# Lightbox_schematic_06NOV.net
KiCad netlist of a schematic drawn in EAGLE
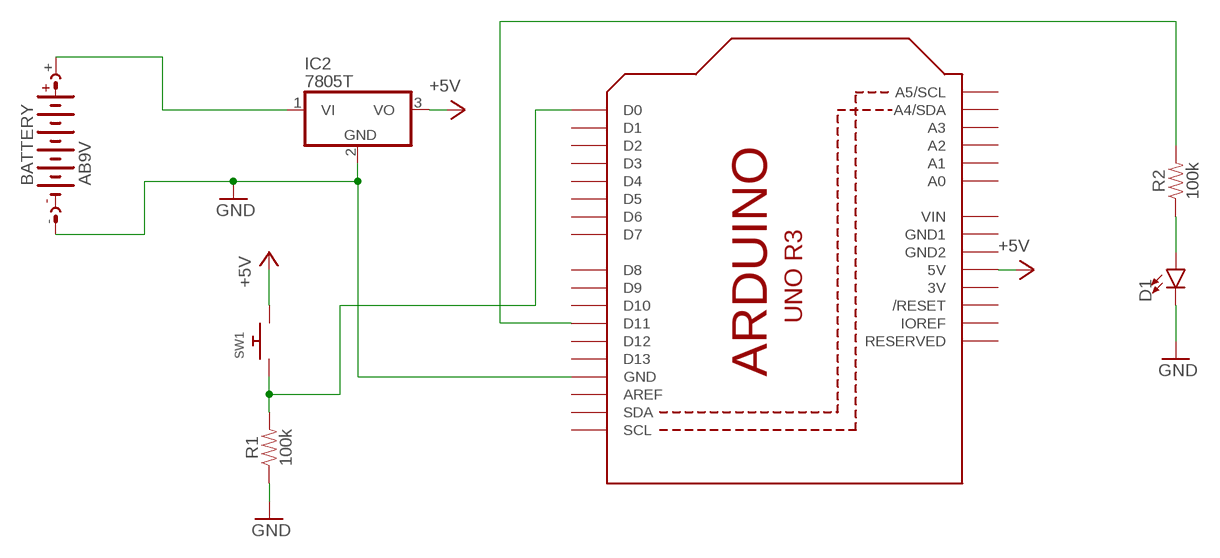
[diagram p0: schematic, sheet 1]

(export (version "E")
  (design (tool "Eeschema 10.0.6"))
  (components
    (comp (ref "BATTERY")
      (value "AB9V")
      (footprint "eagle-import:AB9V")
      (libsource (lib "eagle-import") (part "AB9V"))
    )
    (comp (ref "D1")
      (value "LED3MM")
      (footprint "eagle-import:LED_3MM")
      (libsource (lib "eagle-import") (part "LED3MM"))
    )
    (comp (ref "IC2")
      (value "7805T")
      (footprint "eagle-import:TO220H")
      (libsource (lib "eagle-import") (part "78T05"))
    )
    (comp (ref "R1")
      (value "100k")
      (footprint "eagle-import:AXIAL-0.3")
      (libsource (lib "eagle-import") (part "100KOHM-HORIZ-1/4W-1%"))
    )
    (comp (ref "R2")
      (value "100k")
      (footprint "eagle-import:AXIAL-0.3")
      (libsource (lib "eagle-import") (part "100KOHM-HORIZ-1/4W-1%"))
    )
    (comp (ref "SW1")
      (value "SWITCH_PUSHBUTTONSOFTTOUCHSMD_SJ")
      (footprint "eagle-import:PUSHBUTTON_SMD_SJ")
      (libsource (lib "eagle-import") (part "SWITCH_PUSHBUTTONSOFTTOUCHSMD_SJ"))
    )
    (comp (ref "U1")
      (value "ARDUINOR3-DIMENSION")
      (footprint "eagle-import:ARDUINOR3")
      (libsource (lib "eagle-import") (part "ARDUINOR3-DIMENSION"))
    )
  )
  (nets
    (net (code "1") (name "+5V") (class "Default")
      (node (ref "IC2") (pin "3") (pinfunction "VO_3") (pintype "passive"))
      (node (ref "SW1") (pin "P$2") (pinfunction "P$2_P$2") (pintype "passive"))
      (node (ref "U1") (pin "5V") (pinfunction "5V_5V") (pintype "power_in"))
    )
    (net (code "2") (name "/3V") (class "Default")
      (node (ref "U1") (pin "3V") (pinfunction "3V_3V") (pintype "power_in"))
    )
    (net (code "3") (name "/GND1") (class "Default")
      (node (ref "U1") (pin "GND1") (pinfunction "GND1_GND1") (pintype "power_in"))
    )
    (net (code "4") (name "/GND2") (class "Default")
      (node (ref "U1") (pin "GND2") (pinfunction "GND2_GND2") (pintype "power_in"))
    )
    (net (code "5") (name "/VIN") (class "Default")
      (node (ref "U1") (pin "VIN") (pinfunction "VIN_VIN") (pintype "power_in"))
    )
    (net (code "6") (name "GND") (class "Default")
      (node (ref "BATTERY") (pin "-") (pinfunction "-_-") (pintype "passive"))
      (node (ref "D1") (pin "K") (pinfunction "C_K") (pintype "passive"))
      (node (ref "IC2") (pin "2") (pinfunction "GND_2") (pintype "passive"))
      (node (ref "R1") (pin "P$1") (pinfunction "1_P$1") (pintype "passive"))
      (node (ref "U1") (pin "GND") (pinfunction "GND_GND") (pintype "power_in"))
    )
    (net (code "7") (name "Net-(IC2-VI)") (class "Default")
      (node (ref "BATTERY") (pin "+") (pinfunction "+_+") (pintype "passive"))
      (node (ref "IC2") (pin "1") (pinfunction "VI_1") (pintype "input"))
    )
    (net (code "8") (name "Net-(R1-2)") (class "Default")
      (node (ref "R1") (pin "P$2") (pinfunction "2_P$2") (pintype "passive"))
      (node (ref "SW1") (pin "P$1") (pinfunction "P$1_P$1") (pintype "passive"))
      (node (ref "U1") (pin "D0") (pinfunction "D0_D0") (pintype "bidirectional"))
    )
    (net (code "9") (name "Net-(R2-1)") (class "Default")
      (node (ref "D1") (pin "A") (pinfunction "A_A") (pintype "passive"))
      (node (ref "R2") (pin "P$1") (pinfunction "1_P$1") (pintype "passive"))
    )
    (net (code "10") (name "Net-(R2-2)") (class "Default")
      (node (ref "R2") (pin "P$2") (pinfunction "2_P$2") (pintype "passive"))
      (node (ref "U1") (pin "D11") (pinfunction "D11_D11") (pintype "bidirectional"))
    )
    (net (code "11") (name "unconnected-(U1-A4{slash}SDA-PadA4)") (class "Default")
      (node (ref "U1") (pin "A4") (pinfunction "A4/SDA_A4") (pintype "bidirectional"))
    )
    (net (code "12") (name "unconnected-(U1-A5{slash}SCL-PadA5)") (class "Default")
      (node (ref "U1") (pin "A5") (pinfunction "A5/SCL_A5") (pintype "bidirectional"))
    )
    (net (code "13") (name "unconnected-(U1-PadA0)") (class "Default")
      (node (ref "U1") (pin "A0") (pinfunction "A0_A0") (pintype "bidirectional"))
    )
    (net (code "14") (name "unconnected-(U1-PadA1)") (class "Default")
      (node (ref "U1") (pin "A1") (pinfunction "A1_A1") (pintype "bidirectional"))
    )
    (net (code "15") (name "unconnected-(U1-PadA2)") (class "Default")
      (node (ref "U1") (pin "A2") (pinfunction "A2_A2") (pintype "bidirectional"))
    )
    (net (code "16") (name "unconnected-(U1-PadA3)") (class "Default")
      (node (ref "U1") (pin "A3") (pinfunction "A3_A3") (pintype "bidirectional"))
    )
    (net (code "17") (name "unconnected-(U1-PadAREF)") (class "Default")
      (node (ref "U1") (pin "AREF") (pinfunction "AREF_AREF") (pintype "bidirectional"))
    )
    (net (code "18") (name "unconnected-(U1-PadD1)") (class "Default")
      (node (ref "U1") (pin "D1") (pinfunction "D1_D1") (pintype "bidirectional"))
    )
    (net (code "19") (name "unconnected-(U1-PadD2)") (class "Default")
      (node (ref "U1") (pin "D2") (pinfunction "D2_D2") (pintype "bidirectional"))
    )
    (net (code "20") (name "unconnected-(U1-PadD3)") (class "Default")
      (node (ref "U1") (pin "D3") (pinfunction "D3_D3") (pintype "bidirectional"))
    )
    (net (code "21") (name "unconnected-(U1-PadD4)") (class "Default")
      (node (ref "U1") (pin "D4") (pinfunction "D4_D4") (pintype "bidirectional"))
    )
    (net (code "22") (name "unconnected-(U1-PadD5)") (class "Default")
      (node (ref "U1") (pin "D5") (pinfunction "D5_D5") (pintype "bidirectional"))
    )
    (net (code "23") (name "unconnected-(U1-PadD6)") (class "Default")
      (node (ref "U1") (pin "D6") (pinfunction "D6_D6") (pintype "bidirectional"))
    )
    (net (code "24") (name "unconnected-(U1-PadD7)") (class "Default")
      (node (ref "U1") (pin "D7") (pinfunction "D7_D7") (pintype "bidirectional"))
    )
    (net (code "25") (name "unconnected-(U1-PadD8)") (class "Default")
      (node (ref "U1") (pin "D8") (pinfunction "D8_D8") (pintype "bidirectional"))
    )
    (net (code "26") (name "unconnected-(U1-PadD9)") (class "Default")
      (node (ref "U1") (pin "D9") (pinfunction "D9_D9") (pintype "bidirectional"))
    )
    (net (code "27") (name "unconnected-(U1-PadD10)") (class "Default")
      (node (ref "U1") (pin "D10") (pinfunction "D10_D10") (pintype "bidirectional"))
    )
    (net (code "28") (name "unconnected-(U1-PadD12)") (class "Default")
      (node (ref "U1") (pin "D12") (pinfunction "D12_D12") (pintype "bidirectional"))
    )
    (net (code "29") (name "unconnected-(U1-PadD13)") (class "Default")
      (node (ref "U1") (pin "D13") (pinfunction "D13_D13") (pintype "bidirectional"))
    )
    (net (code "30") (name "unconnected-(U1-PadIOREF)") (class "Default")
      (node (ref "U1") (pin "IOREF") (pinfunction "IOREF_IOREF") (pintype "output"))
    )
    (net (code "31") (name "unconnected-(U1-PadRESERVED)") (class "Default")
      (node (ref "U1") (pin "RESERVED") (pinfunction "RESERVED_RESERVED") (pintype "no_connect"))
    )
    (net (code "32") (name "unconnected-(U1-PadSCL)") (class "Default")
      (node (ref "U1") (pin "SCL") (pinfunction "SCL_SCL") (pintype "bidirectional"))
    )
    (net (code "33") (name "unconnected-(U1-PadSDA)") (class "Default")
      (node (ref "U1") (pin "SDA") (pinfunction "SDA_SDA") (pintype "bidirectional"))
    )
    (net (code "34") (name "unconnected-(U1-{slash}RESET-PadRESET)") (class "Default")
      (node (ref "U1") (pin "RESET") (pinfunction "/RESET_RESET") (pintype "bidirectional"))
    )
  )
)
